# 6_-CHARGER.net
KiCad netlist of a schematic drawn in Altium Designer
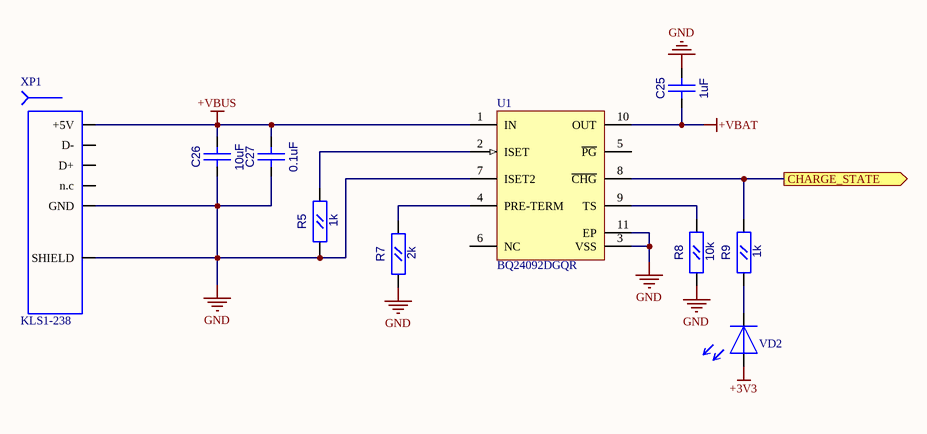
[diagram p0: [6]-CHARGER.SchDoc]

(export (version "E")
  (design (tool "Eeschema 10.0.6"))
  (components
    (comp (ref "C25")
      (value "1uF")
      (footprint "CC0603")
      (description "CC0603")
      (libsource (lib "gprs_modem_2") (part "CC0603"))
    )
    (comp (ref "C26")
      (value "10uF")
      (footprint "CC0805")
      (description "CC0805")
      (libsource (lib "gprs_modem_2") (part "CC0805"))
    )
    (comp (ref "C27")
      (value "0.1uF")
      (footprint "CC0603")
      (description "CC0603")
      (libsource (lib "gprs_modem_2") (part "CC0603"))
    )
    (comp (ref "R5")
      (value "1k")
      (footprint "RC0603")
      (description "RC0603")
      (libsource (lib "gprs_modem_2") (part "RC0603"))
    )
    (comp (ref "R7")
      (value "2k")
      (footprint "RC0603")
      (description "RC0603")
      (libsource (lib "gprs_modem_2") (part "RC0603"))
    )
    (comp (ref "R8")
      (value "10k")
      (footprint "RC0603")
      (description "RC0603")
      (libsource (lib "gprs_modem_2") (part "RC0603"))
    )
    (comp (ref "R9")
      (value "1k")
      (footprint "RC0603")
      (description "RC0603")
      (libsource (lib "gprs_modem_2") (part "RC0603"))
    )
    (comp (ref "U1")
      (value "BQ24092DGQR")
      (footprint "DGQ10-1675X1445TP_N")
      (fields (field (name "MANUFACTURER") "Texas Instruments"))
      (libsource (lib "TI Power Management Battery Management") (part "BQ24092DGQR"))
    )
    (comp (ref "VD2")
      (value "LED_0805")
      (footprint "LED0805")
      (libsource (lib "fizik_lib") (part "LED_0805"))
    )
    (comp (ref "XP1")
      (value "KLS1-238")
      (footprint "KLS1-238")
      (libsource (lib "gprs_modem_2") (part "MicroUSB KLS1-238"))
    )
  )
  (nets
    (net (code "1") (name "+3V3") (class "Default") (node (ref "VD2") (pin "1") (pintype "passive")))
    (net (code "2") (name "+VBAT") (class "Default")
      (node (ref "C25") (pin "1") (pinfunction "A_1") (pintype "passive"))
      (node (ref "U1") (pin "10") (pinfunction "OUT_10") (pintype "power_in"))
    )
    (net (code "3") (name "+VBUS") (class "Default")
      (node (ref "C26") (pin "2") (pinfunction "B_2") (pintype "passive"))
      (node (ref "C27") (pin "2") (pinfunction "B_2") (pintype "passive"))
      (node (ref "U1") (pin "1") (pinfunction "IN_1") (pintype "power_in"))
      (node (ref "XP1") (pin "1") (pinfunction "+5V_1") (pintype "passive"))
    )
    (net (code "4") (name "/CHARGE_STATE") (class "Default")
      (node (ref "R9") (pin "2") (pinfunction "B_2") (pintype "passive"))
      (node (ref "U1") (pin "8") (pinfunction "~{CHG}_8") (pintype "tri_state"))
    )
    (net (code "5") (name "GND") (class "Default")
      (node (ref "C25") (pin "2") (pinfunction "B_2") (pintype "passive"))
      (node (ref "C26") (pin "1") (pinfunction "A_1") (pintype "passive"))
      (node (ref "C27") (pin "1") (pinfunction "A_1") (pintype "passive"))
      (node (ref "R5") (pin "1") (pinfunction "A_1") (pintype "passive"))
      (node (ref "R7") (pin "1") (pinfunction "A_1") (pintype "passive"))
      (node (ref "R8") (pin "1") (pinfunction "A_1") (pintype "passive"))
      (node (ref "U1") (pin "11") (pinfunction "EP_11") (pintype "power_in"))
      (node (ref "U1") (pin "3") (pinfunction "VSS_3") (pintype "power_in"))
      (node (ref "U1") (pin "7") (pinfunction "ISET2_7") (pintype "passive"))
      (node (ref "XP1") (pin "5") (pinfunction "GND_5") (pintype "passive"))
      (node (ref "XP1") (pin "6") (pinfunction "SHIELD_6") (pintype "passive"))
    )
    (net (code "6") (name "Net-(R5-B)") (class "Default")
      (node (ref "R5") (pin "2") (pinfunction "B_2") (pintype "passive"))
      (node (ref "U1") (pin "2") (pinfunction "ISET_2") (pintype "input"))
    )
    (net (code "7") (name "Net-(R7-B)") (class "Default")
      (node (ref "R7") (pin "2") (pinfunction "B_2") (pintype "passive"))
      (node (ref "U1") (pin "4") (pinfunction "PRE-TERM_4") (pintype "passive"))
    )
    (net (code "8") (name "Net-(R8-B)") (class "Default")
      (node (ref "R8") (pin "2") (pinfunction "B_2") (pintype "passive"))
      (node (ref "U1") (pin "9") (pinfunction "TS_9") (pintype "passive"))
    )
    (net (code "9") (name "Net-(R9-A)") (class "Default")
      (node (ref "R9") (pin "1") (pinfunction "A_1") (pintype "passive"))
      (node (ref "VD2") (pin "2") (pintype "passive"))
    )
    (net (code "10") (name "unconnected-(U1-NC-Pad6)") (class "Default")
      (node (ref "U1") (pin "6") (pinfunction "NC_6") (pintype "passive"))
    )
    (net (code "11") (name "unconnected-(U1-~{PG}-Pad5)") (class "Default")
      (node (ref "U1") (pin "5") (pinfunction "~{PG}_5") (pintype "tri_state"))
    )
    (net (code "12") (name "unconnected-(XP1-D+-Pad3)") (class "Default")
      (node (ref "XP1") (pin "3") (pinfunction "D+_3") (pintype "passive"))
    )
    (net (code "13") (name "unconnected-(XP1-D--Pad2)") (class "Default")
      (node (ref "XP1") (pin "2") (pinfunction "D-_2") (pintype "passive"))
    )
    (net (code "14") (name "unconnected-(XP1-n.c-Pad4)") (class "Default")
      (node (ref "XP1") (pin "4") (pinfunction "n.c_4") (pintype "passive"))
    )
  )
)
